# SlimRx.net
KiCad netlist of a schematic drawn in Altium Designer
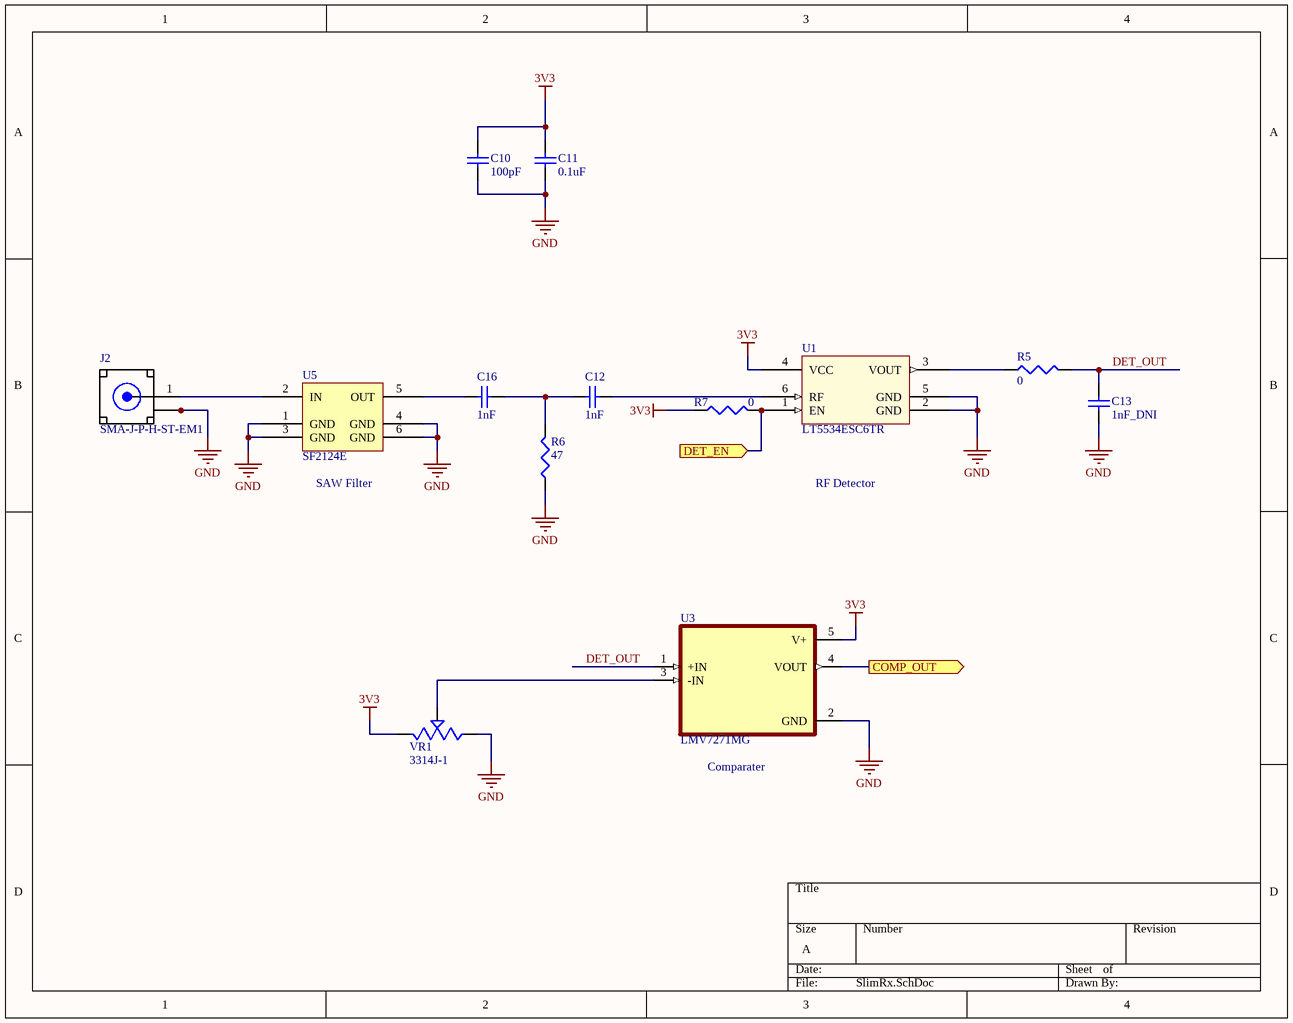
[diagram p0: SlimRx.SchDoc]

(export (version "E")
  (design (tool "Eeschema 10.0.6"))
  (components
    (comp (ref "C10")
      (value "100pF")
      (footprint "SMD-0603")
      (description "Ceramic Capacitor 0603")
      (libsource (lib "LCR") (part "CAP0603"))
    )
    (comp (ref "C11")
      (value "0.1uF")
      (footprint "SMD-0805")
      (description "Ceramic Capacitor 0805 Imperial (2012 Metric)")
      (libsource (lib "LCR") (part "CAP0805"))
    )
    (comp (ref "C12")
      (value "1nF")
      (footprint "SMD-0603")
      (description "Ceramic Capacitor 0603")
      (libsource (lib "LCR") (part "CAP0603"))
    )
    (comp (ref "C13")
      (value "1nF_DNI")
      (footprint "SMD-0603")
      (description "Ceramic Capacitor 0603")
      (libsource (lib "LCR") (part "CAP0603"))
    )
    (comp (ref "C16")
      (value "1nF")
      (footprint "SMD-0603")
      (description "Ceramic Capacitor 0603")
      (libsource (lib "LCR") (part "CAP0603"))
    )
    (comp (ref "J2")
      (value "SMA-J-P-H-ST-EM1")
      (footprint "SMA-J-P-H-ST-EM1")
      (description "Connector SMA F 50Ohm Solder ST Edge Mount Gold Over Nickel Tray")
      (fields (field (name "MF") "Samtec"))
      (libsource (lib "Connectors") (part "SMA-J-P-H-ST-EM1"))
    )
    (comp (ref "R5")
      (value "0")
      (footprint "SMD-0603")
      (description "Resistor-0603")
      (libsource (lib "LCR") (part "RES0603"))
    )
    (comp (ref "R6")
      (value "47")
      (footprint "SMD-0603")
      (description "Resistor-0603")
      (libsource (lib "LCR") (part "RES0603"))
    )
    (comp (ref "R7")
      (value "0")
      (footprint "SMD-0603")
      (description "Resistor-0603")
      (libsource (lib "LCR") (part "RES0603"))
    )
    (comp (ref "U1")
      (value "LT5534ESC6TR")
      (footprint "SOT-6_SC")
      (libsource (lib "LT5534ESC6TR") (part "LT5534ESC6TR"))
    )
    (comp (ref "U3")
      (value "LMV7271MG")
      (footprint "SOT65P210X110-5N")
      (libsource (lib "LMV7271MG") (part "LMV7271MG"))
    )
    (comp (ref "U5")
      (value "SF2124E")
      (footprint "FIL_SF2124E")
      (description "Signal Conditioning FILTER, SAW, 2441.8 MHZ, 6SMD")
      (libsource (lib "saw") (part "SF2124E"))
    )
    (comp (ref "VR1")
      (value "3314J-1")
      (footprint "LCR:TRIM_3314J-1")
      (description "10 kOhms 0.25W, 1/4W J Lead Surface Mount Trimmer Potentiometer Cermet 1 Turn Top Adjustment")
      (fields (field (name "MP") "3314J-1-103E") (field (name "MF") "Bourns"))
      (libsource (lib "LCR") (part "3314J-1"))
    )
  )
  (nets
    (net (code "1") (name "/COMP_OUT") (class "Default")
      (node (ref "U3") (pin "4") (pinfunction "VOUT_4") (pintype "output"))
    )
    (net (code "2") (name "/DET_EN") (class "Default")
      (node (ref "R7") (pin "2") (pinfunction "2_2") (pintype "passive"))
      (node (ref "U1") (pin "1") (pinfunction "EN_1") (pintype "input"))
    )
    (net (code "3") (name "/DET_OUT") (class "Default")
      (node (ref "C13") (pin "2") (pinfunction "2_2") (pintype "passive"))
      (node (ref "R5") (pin "2") (pinfunction "2_2") (pintype "passive"))
      (node (ref "U3") (pin "1") (pinfunction "+IN_1") (pintype "input"))
    )
    (net (code "4") (name "3V3") (class "Default")
      (node (ref "C10") (pin "2") (pinfunction "2_2") (pintype "passive"))
      (node (ref "C11") (pin "2") (pinfunction "2_2") (pintype "passive"))
      (node (ref "R7") (pin "1") (pinfunction "1_1") (pintype "passive"))
      (node (ref "U1") (pin "4") (pinfunction "VCC_4") (pintype "power_in"))
      (node (ref "U3") (pin "5") (pinfunction "V+_5") (pintype "power_in"))
      (node (ref "VR1") (pin "1") (pinfunction "CCW_1") (pintype "passive"))
    )
    (net (code "5") (name "GND") (class "Default")
      (node (ref "C10") (pin "1") (pinfunction "1_1") (pintype "passive"))
      (node (ref "C11") (pin "1") (pinfunction "1_1") (pintype "passive"))
      (node (ref "C13") (pin "1") (pinfunction "1_1") (pintype "passive"))
      (node (ref "J2") (pin "2_1") (pinfunction "GND_2_1") (pintype "power_in"))
      (node (ref "J2") (pin "2_2") (pinfunction "GND_2_2") (pintype "power_in"))
      (node (ref "J2") (pin "3_1") (pinfunction "GND_3_1") (pintype "power_in"))
      (node (ref "J2") (pin "3_2") (pinfunction "GND_3_2") (pintype "power_in"))
      (node (ref "R6") (pin "1") (pinfunction "1_1") (pintype "passive"))
      (node (ref "U1") (pin "2") (pinfunction "GND_2") (pintype "power_in"))
      (node (ref "U1") (pin "5") (pinfunction "GND_5") (pintype "power_in"))
      (node (ref "U3") (pin "2") (pinfunction "GND_2") (pintype "power_in"))
      (node (ref "U5") (pin "1") (pinfunction "GND_1") (pintype "passive"))
      (node (ref "U5") (pin "3") (pinfunction "GND_3") (pintype "passive"))
      (node (ref "U5") (pin "4") (pinfunction "GND_4") (pintype "passive"))
      (node (ref "U5") (pin "6") (pinfunction "GND_6") (pintype "passive"))
      (node (ref "VR1") (pin "3") (pinfunction "CW_3") (pintype "passive"))
    )
    (net (code "6") (name "Net-(C12-Pad1)") (class "Default")
      (node (ref "C12") (pin "1") (pinfunction "1_1") (pintype "passive"))
      (node (ref "C16") (pin "2") (pinfunction "2_2") (pintype "passive"))
      (node (ref "R6") (pin "2") (pinfunction "2_2") (pintype "passive"))
    )
    (net (code "7") (name "Net-(J2-SIGNAL)") (class "Default")
      (node (ref "J2") (pin "1") (pinfunction "SIGNAL_1") (pintype "passive"))
      (node (ref "U5") (pin "2") (pinfunction "IN_2") (pintype "passive"))
    )
    (net (code "8") (name "Net-(U1-RF)") (class "Default")
      (node (ref "C12") (pin "2") (pinfunction "2_2") (pintype "passive"))
      (node (ref "U1") (pin "6") (pinfunction "RF_6") (pintype "input"))
    )
    (net (code "9") (name "Net-(U1-VOUT)") (class "Default")
      (node (ref "R5") (pin "1") (pinfunction "1_1") (pintype "passive"))
      (node (ref "U1") (pin "3") (pinfunction "VOUT_3") (pintype "output"))
    )
    (net (code "10") (name "Net-(U3--IN)") (class "Default")
      (node (ref "U3") (pin "3") (pinfunction "-IN_3") (pintype "input"))
      (node (ref "VR1") (pin "2") (pinfunction "WIPER_2") (pintype "passive"))
    )
    (net (code "11") (name "Net-(U5-OUT)") (class "Default")
      (node (ref "C16") (pin "1") (pinfunction "1_1") (pintype "passive"))
      (node (ref "U5") (pin "5") (pinfunction "OUT_5") (pintype "passive"))
    )
  )
)
